# rpi_midi.net
KiCad netlist of a schematic drawn in EAGLE
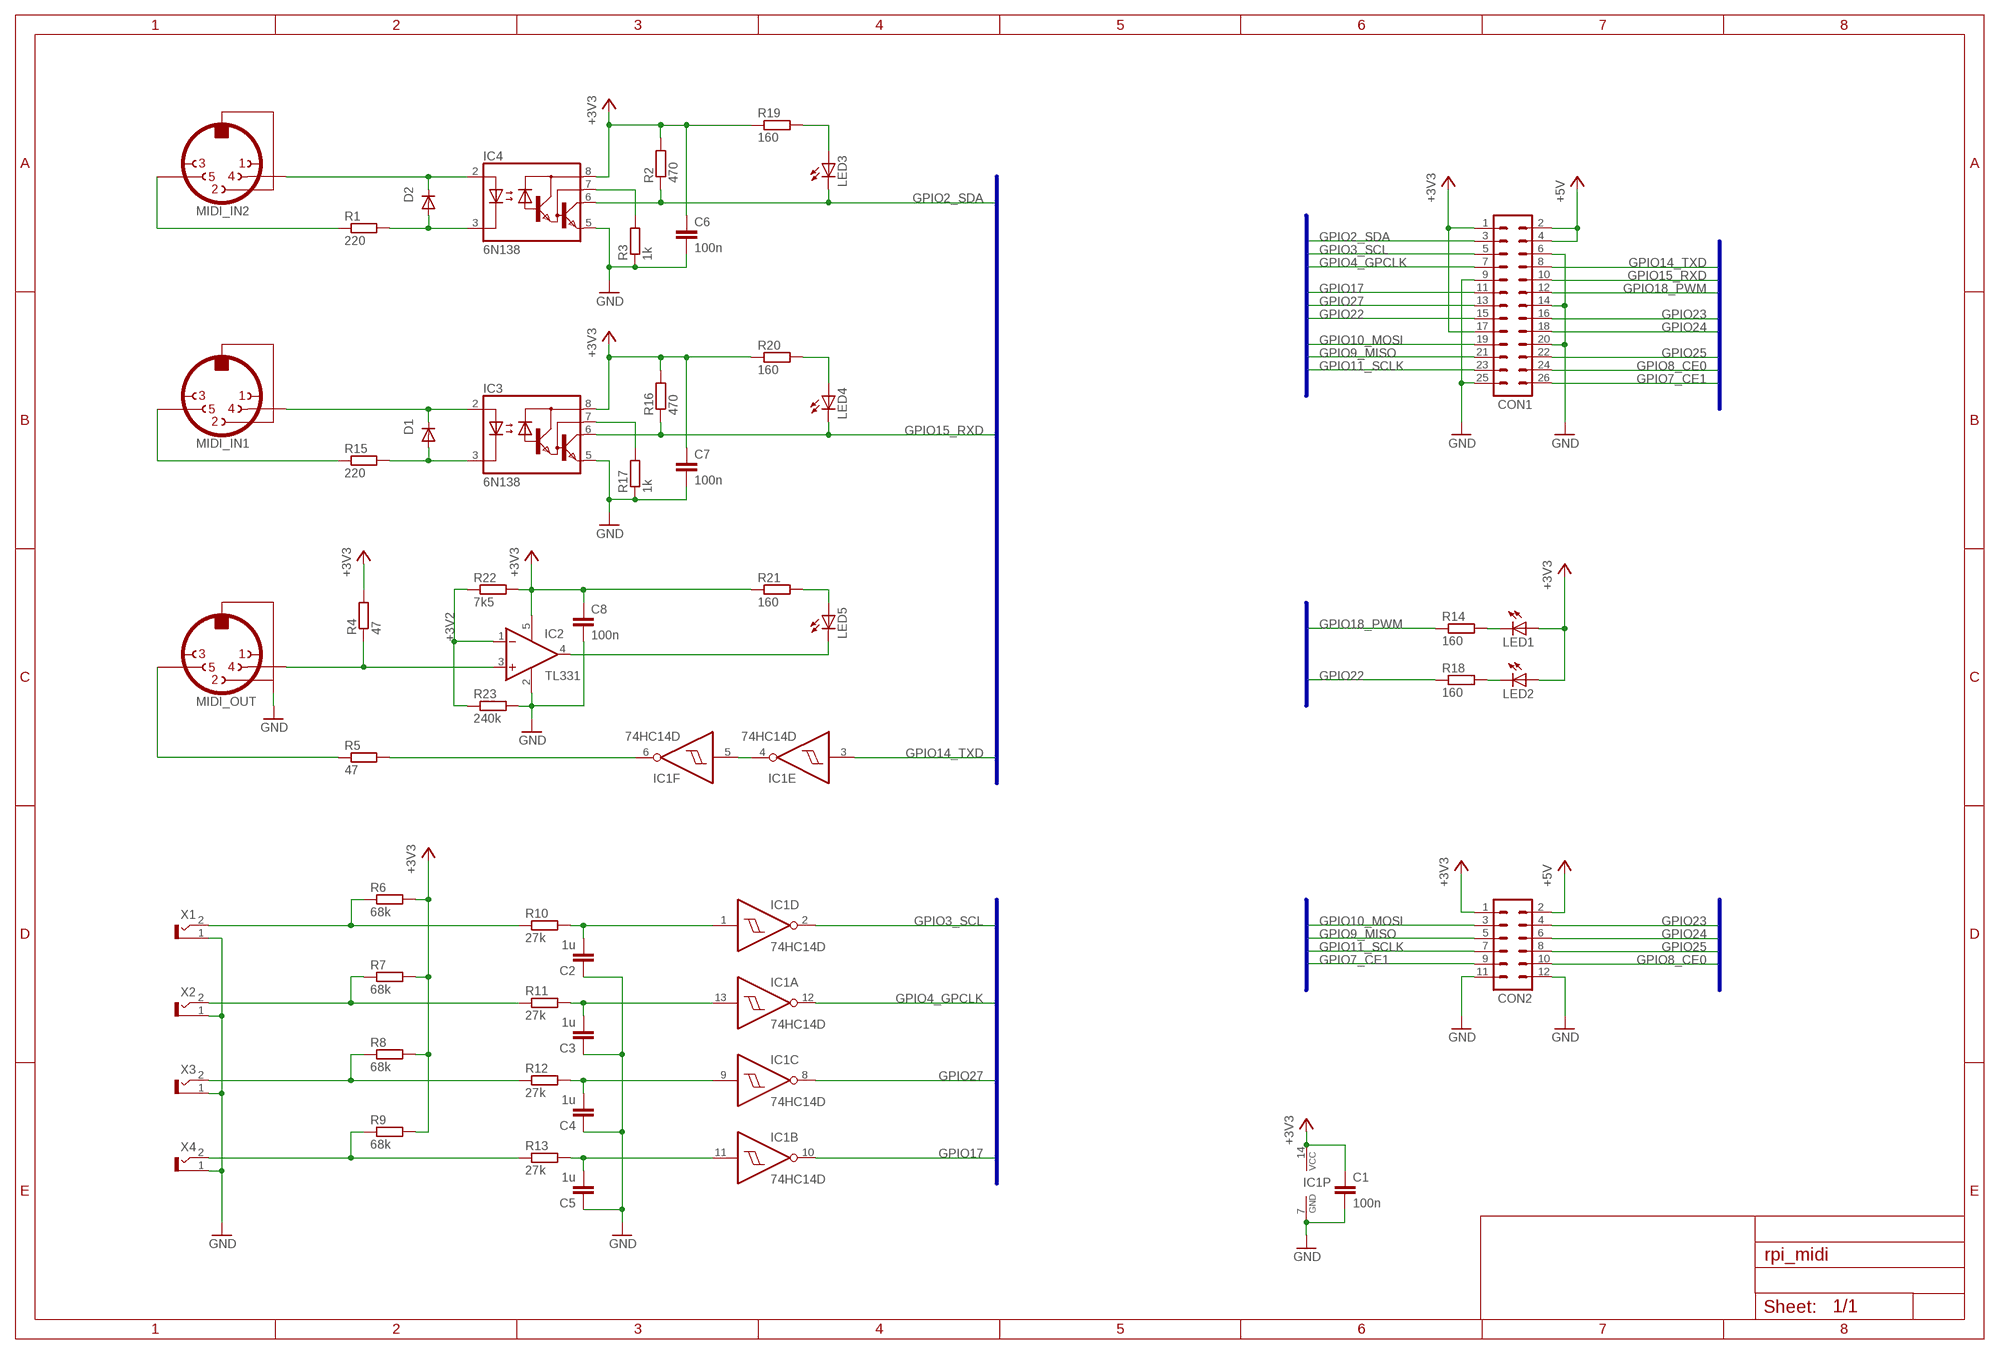
[diagram p0: schematic, sheet 1]

(export (version "E")
  (design (tool "Eeschema 10.0.6"))
  (components
    (comp (ref "C1")
      (value "100n")
      (footprint "eagle-import:C0603")
      (libsource (lib "eagle-import") (part "C-EUC0603"))
    )
    (comp (ref "C2")
      (value "1u")
      (footprint "eagle-import:C0603")
      (libsource (lib "eagle-import") (part "C-EUC0603"))
    )
    (comp (ref "C3")
      (value "1u")
      (footprint "eagle-import:C0603")
      (libsource (lib "eagle-import") (part "C-EUC0603"))
    )
    (comp (ref "C4")
      (value "1u")
      (footprint "eagle-import:C0603")
      (libsource (lib "eagle-import") (part "C-EUC0603"))
    )
    (comp (ref "C5")
      (value "1u")
      (footprint "eagle-import:C0603")
      (libsource (lib "eagle-import") (part "C-EUC0603"))
    )
    (comp (ref "C6")
      (value "100n")
      (footprint "eagle-import:C0603")
      (libsource (lib "eagle-import") (part "C-EUC0603"))
    )
    (comp (ref "C7")
      (value "100n")
      (footprint "eagle-import:C0603")
      (libsource (lib "eagle-import") (part "C-EUC0603"))
    )
    (comp (ref "C8")
      (value "100n")
      (footprint "eagle-import:C0603")
      (libsource (lib "eagle-import") (part "C-EUC0603"))
    )
    (comp (ref "CON1")
      (value "MA13-2")
      (footprint "eagle-import:MA13-2")
      (libsource (lib "eagle-import") (part "MA13-2"))
    )
    (comp (ref "CON2")
      (value "MA06-2")
      (footprint "eagle-import:MA06-2")
      (libsource (lib "eagle-import") (part "MA06-2"))
    )
    (comp (ref "D1")
      (value "1N4148SOD-323")
      (footprint "eagle-import:SOD323-R")
      (libsource (lib "eagle-import") (part "1N4148SOD-323"))
    )
    (comp (ref "D2")
      (value "1N4148SOD-323")
      (footprint "eagle-import:SOD323-R")
      (libsource (lib "eagle-import") (part "1N4148SOD-323"))
    )
    (comp (ref "IC1")
      (value "74HC14D")
      (footprint "eagle-import:SO14")
      (libsource (lib "eagle-import") (part "7414DHC"))
    )
    (comp (ref "IC2")
      (value "TL331")
      (footprint "eagle-import:SOT23-DBV")
      (libsource (lib "eagle-import") (part "TL331"))
    )
    (comp (ref "IC3")
      (value "6N138")
      (footprint "eagle-import:DIL08")
      (fields (field (name "MF") "VISHAY/TELEFUNKEN"))
      (libsource (lib "eagle-import") (part "6N138"))
    )
    (comp (ref "IC4")
      (value "6N138")
      (footprint "eagle-import:DIL08")
      (fields (field (name "MF") "VISHAY/TELEFUNKEN"))
      (libsource (lib "eagle-import") (part "6N138"))
    )
    (comp (ref "LED1")
      (value "LED2.54MM")
      (footprint "eagle-import:HEADER_2X1")
      (libsource (lib "eagle-import") (part "LED2.54MM"))
    )
    (comp (ref "LED2")
      (value "LED2.54MM")
      (footprint "eagle-import:HEADER_2X1")
      (libsource (lib "eagle-import") (part "LED2.54MM"))
    )
    (comp (ref "LED3")
      (value "LED2.54MM")
      (footprint "eagle-import:HEADER_2X1")
      (libsource (lib "eagle-import") (part "LED2.54MM"))
    )
    (comp (ref "LED4")
      (value "LED2.54MM")
      (footprint "eagle-import:HEADER_2X1")
      (libsource (lib "eagle-import") (part "LED2.54MM"))
    )
    (comp (ref "LED5")
      (value "LED2.54MM")
      (footprint "eagle-import:HEADER_2X1")
      (libsource (lib "eagle-import") (part "LED2.54MM"))
    )
    (comp (ref "MIDI_IN1")
      (value "MIDI_2PIN")
      (footprint "eagle-import:HEADER_2X1")
      (libsource (lib "eagle-import") (part "MIDI_2PIN"))
    )
    (comp (ref "MIDI_IN2")
      (value "MIDI_2PIN")
      (footprint "eagle-import:HEADER_2X1")
      (libsource (lib "eagle-import") (part "MIDI_2PIN"))
    )
    (comp (ref "MIDI_OUT")
      (value "MIDI_3PIN")
      (footprint "eagle-import:HEADER_3X1")
      (libsource (lib "eagle-import") (part "MIDI_3PIN"))
    )
    (comp (ref "R1")
      (value "220")
      (footprint "eagle-import:R0603")
      (libsource (lib "eagle-import") (part "R-EU_R0603"))
    )
    (comp (ref "R2")
      (value "470")
      (footprint "eagle-import:R0603")
      (libsource (lib "eagle-import") (part "R-EU_R0603"))
    )
    (comp (ref "R3")
      (value "1k")
      (footprint "eagle-import:R0603")
      (libsource (lib "eagle-import") (part "R-EU_R0603"))
    )
    (comp (ref "R4")
      (value "47")
      (footprint "eagle-import:R0603")
      (libsource (lib "eagle-import") (part "R-EU_R0603"))
    )
    (comp (ref "R5")
      (value "47")
      (footprint "eagle-import:R0603")
      (libsource (lib "eagle-import") (part "R-EU_R0603"))
    )
    (comp (ref "R6")
      (value "68k")
      (footprint "eagle-import:R0603")
      (libsource (lib "eagle-import") (part "R-EU_R0603"))
    )
    (comp (ref "R7")
      (value "68k")
      (footprint "eagle-import:R0603")
      (libsource (lib "eagle-import") (part "R-EU_R0603"))
    )
    (comp (ref "R8")
      (value "68k")
      (footprint "eagle-import:R0603")
      (libsource (lib "eagle-import") (part "R-EU_R0603"))
    )
    (comp (ref "R9")
      (value "68k")
      (footprint "eagle-import:R0603")
      (libsource (lib "eagle-import") (part "R-EU_R0603"))
    )
    (comp (ref "R10")
      (value "27k")
      (footprint "eagle-import:R0603")
      (libsource (lib "eagle-import") (part "R-EU_R0603"))
    )
    (comp (ref "R11")
      (value "27k")
      (footprint "eagle-import:R0603")
      (libsource (lib "eagle-import") (part "R-EU_R0603"))
    )
    (comp (ref "R12")
      (value "27k")
      (footprint "eagle-import:R0603")
      (libsource (lib "eagle-import") (part "R-EU_R0603"))
    )
    (comp (ref "R13")
      (value "27k")
      (footprint "eagle-import:R0603")
      (libsource (lib "eagle-import") (part "R-EU_R0603"))
    )
    (comp (ref "R14")
      (value "160")
      (footprint "eagle-import:R0603")
      (libsource (lib "eagle-import") (part "R-EU_R0603"))
    )
    (comp (ref "R15")
      (value "220")
      (footprint "eagle-import:R0603")
      (libsource (lib "eagle-import") (part "R-EU_R0603"))
    )
    (comp (ref "R16")
      (value "470")
      (footprint "eagle-import:R0603")
      (libsource (lib "eagle-import") (part "R-EU_R0603"))
    )
    (comp (ref "R17")
      (value "1k")
      (footprint "eagle-import:R0603")
      (libsource (lib "eagle-import") (part "R-EU_R0603"))
    )
    (comp (ref "R18")
      (value "160")
      (footprint "eagle-import:R0603")
      (libsource (lib "eagle-import") (part "R-EU_R0603"))
    )
    (comp (ref "R19")
      (value "160")
      (footprint "eagle-import:R0603")
      (libsource (lib "eagle-import") (part "R-EU_R0603"))
    )
    (comp (ref "R20")
      (value "160")
      (footprint "eagle-import:R0603")
      (libsource (lib "eagle-import") (part "R-EU_R0603"))
    )
    (comp (ref "R21")
      (value "160")
      (footprint "eagle-import:R0603")
      (libsource (lib "eagle-import") (part "R-EU_R0603"))
    )
    (comp (ref "R22")
      (value "7k5")
      (footprint "eagle-import:R0603")
      (libsource (lib "eagle-import") (part "R-EU_R0603"))
    )
    (comp (ref "R23")
      (value "240k")
      (footprint "eagle-import:R0603")
      (libsource (lib "eagle-import") (part "R-EU_R0603"))
    )
    (comp (ref "X1")
      (value "WBTOR12.54MM")
      (footprint "eagle-import:HEADER_2X1")
      (libsource (lib "eagle-import") (part "WBTOR12.54MM"))
    )
    (comp (ref "X2")
      (value "WBTOR12.54MM")
      (footprint "eagle-import:HEADER_2X1")
      (libsource (lib "eagle-import") (part "WBTOR12.54MM"))
    )
    (comp (ref "X3")
      (value "WBTOR12.54MM")
      (footprint "eagle-import:HEADER_2X1")
      (libsource (lib "eagle-import") (part "WBTOR12.54MM"))
    )
    (comp (ref "X4")
      (value "WBTOR12.54MM")
      (footprint "eagle-import:HEADER_2X1")
      (libsource (lib "eagle-import") (part "WBTOR12.54MM"))
    )
  )
  (nets
    (net (code "1") (name "+3V3") (class "Default")
      (node (ref "C1") (pin "1") (pinfunction "1_1") (pintype "passive"))
      (node (ref "C6") (pin "1") (pinfunction "1_1") (pintype "passive"))
      (node (ref "C7") (pin "1") (pinfunction "1_1") (pintype "passive"))
      (node (ref "C8") (pin "1") (pinfunction "1_1") (pintype "passive"))
      (node (ref "CON1") (pin "1") (pinfunction "1_1") (pintype "passive"))
      (node (ref "CON1") (pin "17") (pinfunction "17_17") (pintype "passive"))
      (node (ref "CON2") (pin "1") (pinfunction "1_1") (pintype "passive"))
      (node (ref "IC1") (pin "14") (pinfunction "VCC_14") (pintype "power_in"))
      (node (ref "IC2") (pin "5") (pinfunction "V+_5") (pintype "power_in"))
      (node (ref "IC3") (pin "8") (pinfunction "VCC_8") (pintype "passive"))
      (node (ref "IC4") (pin "8") (pinfunction "VCC_8") (pintype "passive"))
      (node (ref "LED1") (pin "1") (pinfunction "A_1") (pintype "passive"))
      (node (ref "LED2") (pin "1") (pinfunction "A_1") (pintype "passive"))
      (node (ref "R16") (pin "2") (pinfunction "2_2") (pintype "passive"))
      (node (ref "R19") (pin "1") (pinfunction "1_1") (pintype "passive"))
      (node (ref "R2") (pin "2") (pinfunction "2_2") (pintype "passive"))
      (node (ref "R20") (pin "1") (pinfunction "1_1") (pintype "passive"))
      (node (ref "R21") (pin "1") (pinfunction "1_1") (pintype "passive"))
      (node (ref "R22") (pin "2") (pinfunction "2_2") (pintype "passive"))
      (node (ref "R4") (pin "2") (pinfunction "2_2") (pintype "passive"))
      (node (ref "R6") (pin "2") (pinfunction "2_2") (pintype "passive"))
      (node (ref "R7") (pin "2") (pinfunction "2_2") (pintype "passive"))
      (node (ref "R8") (pin "2") (pinfunction "2_2") (pintype "passive"))
      (node (ref "R9") (pin "2") (pinfunction "2_2") (pintype "passive"))
    )
    (net (code "2") (name "+5V") (class "Default")
      (node (ref "CON1") (pin "2") (pinfunction "2_2") (pintype "passive"))
      (node (ref "CON1") (pin "4") (pinfunction "4_4") (pintype "passive"))
      (node (ref "CON2") (pin "2") (pinfunction "2_2") (pintype "passive"))
    )
    (net (code "3") (name "/+3V2") (class "Default")
      (node (ref "IC2") (pin "1") (pinfunction "-IN_1") (pintype "input"))
      (node (ref "R22") (pin "1") (pinfunction "1_1") (pintype "passive"))
      (node (ref "R23") (pin "1") (pinfunction "1_1") (pintype "passive"))
    )
    (net (code "4") (name "/GPIO2_SDA") (class "Default")
      (node (ref "CON1") (pin "3") (pinfunction "3_3") (pintype "passive"))
      (node (ref "IC4") (pin "6") (pinfunction "VO_6") (pintype "passive"))
      (node (ref "LED3") (pin "2") (pinfunction "C_2") (pintype "passive"))
      (node (ref "R2") (pin "1") (pinfunction "1_1") (pintype "passive"))
    )
    (net (code "5") (name "/GPIO3_SCL") (class "Default")
      (node (ref "CON1") (pin "5") (pinfunction "5_5") (pintype "passive"))
      (node (ref "IC1") (pin "2") (pinfunction "O_2") (pintype "output"))
    )
    (net (code "6") (name "/GPIO4_GPCLK") (class "Default")
      (node (ref "CON1") (pin "7") (pinfunction "7_7") (pintype "passive"))
      (node (ref "IC1") (pin "12") (pinfunction "O_12") (pintype "output"))
    )
    (net (code "7") (name "/GPIO7_CE1") (class "Default")
      (node (ref "CON1") (pin "26") (pinfunction "26_26") (pintype "passive"))
      (node (ref "CON2") (pin "9") (pinfunction "9_9") (pintype "passive"))
    )
    (net (code "8") (name "/GPIO8_CE0") (class "Default")
      (node (ref "CON1") (pin "24") (pinfunction "24_24") (pintype "passive"))
      (node (ref "CON2") (pin "10") (pinfunction "10_10") (pintype "passive"))
    )
    (net (code "9") (name "/GPIO9_MISO") (class "Default")
      (node (ref "CON1") (pin "21") (pinfunction "21_21") (pintype "passive"))
      (node (ref "CON2") (pin "5") (pinfunction "5_5") (pintype "passive"))
    )
    (net (code "10") (name "/GPIO10_MOSI") (class "Default")
      (node (ref "CON1") (pin "19") (pinfunction "19_19") (pintype "passive"))
      (node (ref "CON2") (pin "3") (pinfunction "3_3") (pintype "passive"))
    )
    (net (code "11") (name "/GPIO11_SCLK") (class "Default")
      (node (ref "CON1") (pin "23") (pinfunction "23_23") (pintype "passive"))
      (node (ref "CON2") (pin "7") (pinfunction "7_7") (pintype "passive"))
    )
    (net (code "12") (name "/GPIO14_TXD") (class "Default")
      (node (ref "CON1") (pin "8") (pinfunction "8_8") (pintype "passive"))
      (node (ref "IC1") (pin "3") (pinfunction "I_3") (pintype "input"))
    )
    (net (code "13") (name "/GPIO15_RXD") (class "Default")
      (node (ref "CON1") (pin "10") (pinfunction "10_10") (pintype "passive"))
      (node (ref "IC3") (pin "6") (pinfunction "VO_6") (pintype "passive"))
      (node (ref "LED4") (pin "2") (pinfunction "C_2") (pintype "passive"))
      (node (ref "R16") (pin "1") (pinfunction "1_1") (pintype "passive"))
    )
    (net (code "14") (name "/GPIO17") (class "Default")
      (node (ref "CON1") (pin "11") (pinfunction "11_11") (pintype "passive"))
      (node (ref "IC1") (pin "10") (pinfunction "O_10") (pintype "output"))
    )
    (net (code "15") (name "/GPIO18_PWM") (class "Default")
      (node (ref "CON1") (pin "12") (pinfunction "12_12") (pintype "passive"))
      (node (ref "R14") (pin "1") (pinfunction "1_1") (pintype "passive"))
    )
    (net (code "16") (name "/GPIO22") (class "Default")
      (node (ref "CON1") (pin "15") (pinfunction "15_15") (pintype "passive"))
      (node (ref "R18") (pin "1") (pinfunction "1_1") (pintype "passive"))
    )
    (net (code "17") (name "/GPIO23") (class "Default")
      (node (ref "CON1") (pin "16") (pinfunction "16_16") (pintype "passive"))
      (node (ref "CON2") (pin "4") (pinfunction "4_4") (pintype "passive"))
    )
    (net (code "18") (name "/GPIO24") (class "Default")
      (node (ref "CON1") (pin "18") (pinfunction "18_18") (pintype "passive"))
      (node (ref "CON2") (pin "6") (pinfunction "6_6") (pintype "passive"))
    )
    (net (code "19") (name "/GPIO25") (class "Default")
      (node (ref "CON1") (pin "22") (pinfunction "22_22") (pintype "passive"))
      (node (ref "CON2") (pin "8") (pinfunction "8_8") (pintype "passive"))
    )
    (net (code "20") (name "/GPIO27") (class "Default")
      (node (ref "CON1") (pin "13") (pinfunction "13_13") (pintype "passive"))
      (node (ref "IC1") (pin "8") (pinfunction "O_8") (pintype "output"))
    )
    (net (code "21") (name "GND") (class "Default")
      (node (ref "C1") (pin "2") (pinfunction "2_2") (pintype "passive"))
      (node (ref "C2") (pin "1") (pinfunction "1_1") (pintype "passive"))
      (node (ref "C3") (pin "1") (pinfunction "1_1") (pintype "passive"))
      (node (ref "C4") (pin "1") (pinfunction "1_1") (pintype "passive"))
      (node (ref "C5") (pin "1") (pinfunction "1_1") (pintype "passive"))
      (node (ref "C6") (pin "2") (pinfunction "2_2") (pintype "passive"))
      (node (ref "C7") (pin "2") (pinfunction "2_2") (pintype "passive"))
      (node (ref "C8") (pin "2") (pinfunction "2_2") (pintype "passive"))
      (node (ref "CON1") (pin "14") (pinfunction "14_14") (pintype "passive"))
      (node (ref "CON1") (pin "20") (pinfunction "20_20") (pintype "passive"))
      (node (ref "CON1") (pin "25") (pinfunction "25_25") (pintype "passive"))
      (node (ref "CON1") (pin "6") (pinfunction "6_6") (pintype "passive"))
      (node (ref "CON1") (pin "9") (pinfunction "9_9") (pintype "passive"))
      (node (ref "CON2") (pin "11") (pinfunction "11_11") (pintype "passive"))
      (node (ref "CON2") (pin "12") (pinfunction "12_12") (pintype "passive"))
      (node (ref "IC1") (pin "7") (pinfunction "GND_7") (pintype "power_in"))
      (node (ref "IC2") (pin "2") (pinfunction "V-_2") (pintype "power_in"))
      (node (ref "IC3") (pin "5") (pinfunction "GND_5") (pintype "passive"))
      (node (ref "IC4") (pin "5") (pinfunction "GND_5") (pintype "passive"))
      (node (ref "MIDI_OUT") (pin "3") (pinfunction "PE_3") (pintype "power_in"))
      (node (ref "R17") (pin "1") (pinfunction "1_1") (pintype "passive"))
      (node (ref "R23") (pin "2") (pinfunction "2_2") (pintype "passive"))
      (node (ref "R3") (pin "1") (pinfunction "1_1") (pintype "passive"))
      (node (ref "X1") (pin "1") (pinfunction "S_1") (pintype "passive"))
      (node (ref "X2") (pin "1") (pinfunction "S_1") (pintype "passive"))
      (node (ref "X3") (pin "1") (pinfunction "S_1") (pintype "passive"))
      (node (ref "X4") (pin "1") (pinfunction "S_1") (pintype "passive"))
    )
    (net (code "22") (name "Net-(IC1A-I)") (class "Default")
      (node (ref "C3") (pin "2") (pinfunction "2_2") (pintype "passive"))
      (node (ref "IC1") (pin "13") (pinfunction "I_13") (pintype "input"))
      (node (ref "R11") (pin "2") (pinfunction "2_2") (pintype "passive"))
    )
    (net (code "23") (name "Net-(IC1B-I)") (class "Default")
      (node (ref "C5") (pin "2") (pinfunction "2_2") (pintype "passive"))
      (node (ref "IC1") (pin "11") (pinfunction "I_11") (pintype "input"))
      (node (ref "R13") (pin "2") (pinfunction "2_2") (pintype "passive"))
    )
    (net (code "24") (name "Net-(IC1C-I)") (class "Default")
      (node (ref "C4") (pin "2") (pinfunction "2_2") (pintype "passive"))
      (node (ref "IC1") (pin "9") (pinfunction "I_9") (pintype "input"))
      (node (ref "R12") (pin "2") (pinfunction "2_2") (pintype "passive"))
    )
    (net (code "25") (name "Net-(IC1D-I)") (class "Default")
      (node (ref "C2") (pin "2") (pinfunction "2_2") (pintype "passive"))
      (node (ref "IC1") (pin "1") (pinfunction "I_1") (pintype "input"))
      (node (ref "R10") (pin "2") (pinfunction "2_2") (pintype "passive"))
    )
    (net (code "26") (name "Net-(IC1E-O)") (class "Default")
      (node (ref "IC1") (pin "4") (pinfunction "O_4") (pintype "output"))
      (node (ref "IC1") (pin "5") (pinfunction "I_5") (pintype "input"))
    )
    (net (code "27") (name "Net-(IC1F-O)") (class "Default")
      (node (ref "IC1") (pin "6") (pinfunction "O_6") (pintype "output"))
      (node (ref "R5") (pin "2") (pinfunction "2_2") (pintype "passive"))
    )
    (net (code "28") (name "Net-(IC2-+IN)") (class "Default")
      (node (ref "IC2") (pin "3") (pinfunction "+IN_3") (pintype "input"))
      (node (ref "MIDI_OUT") (pin "1") (pinfunction "4_1") (pintype "passive"))
      (node (ref "R4") (pin "1") (pinfunction "1_1") (pintype "passive"))
    )
    (net (code "29") (name "Net-(IC2-OUT)") (class "Default")
      (node (ref "IC2") (pin "4") (pinfunction "OUT_4") (pintype "output"))
      (node (ref "LED5") (pin "2") (pinfunction "C_2") (pintype "passive"))
    )
    (net (code "30") (name "Net-(IC3-A)") (class "Default")
      (node (ref "D1") (pin "C") (pinfunction "C_C") (pintype "passive"))
      (node (ref "IC3") (pin "2") (pinfunction "A_2") (pintype "passive"))
      (node (ref "MIDI_IN1") (pin "1") (pinfunction "4_1") (pintype "passive"))
    )
    (net (code "31") (name "Net-(IC3-C)") (class "Default")
      (node (ref "D1") (pin "A") (pinfunction "A_A") (pintype "passive"))
      (node (ref "IC3") (pin "3") (pinfunction "C_3") (pintype "passive"))
      (node (ref "R15") (pin "2") (pinfunction "2_2") (pintype "passive"))
    )
    (net (code "32") (name "Net-(IC3-VB)") (class "Default")
      (node (ref "IC3") (pin "7") (pinfunction "VB_7") (pintype "passive"))
      (node (ref "R17") (pin "2") (pinfunction "2_2") (pintype "passive"))
    )
    (net (code "33") (name "Net-(IC4-A)") (class "Default")
      (node (ref "D2") (pin "C") (pinfunction "C_C") (pintype "passive"))
      (node (ref "IC4") (pin "2") (pinfunction "A_2") (pintype "passive"))
      (node (ref "MIDI_IN2") (pin "1") (pinfunction "4_1") (pintype "passive"))
    )
    (net (code "34") (name "Net-(IC4-C)") (class "Default")
      (node (ref "D2") (pin "A") (pinfunction "A_A") (pintype "passive"))
      (node (ref "IC4") (pin "3") (pinfunction "C_3") (pintype "passive"))
      (node (ref "R1") (pin "2") (pinfunction "2_2") (pintype "passive"))
    )
    (net (code "35") (name "Net-(IC4-VB)") (class "Default")
      (node (ref "IC4") (pin "7") (pinfunction "VB_7") (pintype "passive"))
      (node (ref "R3") (pin "2") (pinfunction "2_2") (pintype "passive"))
    )
    (net (code "36") (name "Net-(LED1-C)") (class "Default")
      (node (ref "LED1") (pin "2") (pinfunction "C_2") (pintype "passive"))
      (node (ref "R14") (pin "2") (pinfunction "2_2") (pintype "passive"))
    )
    (net (code "37") (name "Net-(LED2-C)") (class "Default")
      (node (ref "LED2") (pin "2") (pinfunction "C_2") (pintype "passive"))
      (node (ref "R18") (pin "2") (pinfunction "2_2") (pintype "passive"))
    )
    (net (code "38") (name "Net-(LED3-A)") (class "Default")
      (node (ref "LED3") (pin "1") (pinfunction "A_1") (pintype "passive"))
      (node (ref "R19") (pin "2") (pinfunction "2_2") (pintype "passive"))
    )
    (net (code "39") (name "Net-(LED4-A)") (class "Default")
      (node (ref "LED4") (pin "1") (pinfunction "A_1") (pintype "passive"))
      (node (ref "R20") (pin "2") (pinfunction "2_2") (pintype "passive"))
    )
    (net (code "40") (name "Net-(LED5-A)") (class "Default")
      (node (ref "LED5") (pin "1") (pinfunction "A_1") (pintype "passive"))
      (node (ref "R21") (pin "2") (pinfunction "2_2") (pintype "passive"))
    )
    (net (code "41") (name "Net-(MIDI_IN1-5)") (class "Default")
      (node (ref "MIDI_IN1") (pin "2") (pinfunction "5_2") (pintype "passive"))
      (node (ref "R15") (pin "1") (pinfunction "1_1") (pintype "passive"))
    )
    (net (code "42") (name "Net-(MIDI_IN2-5)") (class "Default")
      (node (ref "MIDI_IN2") (pin "2") (pinfunction "5_2") (pintype "passive"))
      (node (ref "R1") (pin "1") (pinfunction "1_1") (pintype "passive"))
    )
    (net (code "43") (name "Net-(MIDI_OUT-5)") (class "Default")
      (node (ref "MIDI_OUT") (pin "2") (pinfunction "5_2") (pintype "passive"))
      (node (ref "R5") (pin "1") (pinfunction "1_1") (pintype "passive"))
    )
    (net (code "44") (name "Net-(X1-T)") (class "Default")
      (node (ref "R10") (pin "1") (pinfunction "1_1") (pintype "passive"))
      (node (ref "R6") (pin "1") (pinfunction "1_1") (pintype "passive"))
      (node (ref "X1") (pin "2") (pinfunction "T_2") (pintype "passive"))
    )
    (net (code "45") (name "Net-(X2-T)") (class "Default")
      (node (ref "R11") (pin "1") (pinfunction "1_1") (pintype "passive"))
      (node (ref "R7") (pin "1") (pinfunction "1_1") (pintype "passive"))
      (node (ref "X2") (pin "2") (pinfunction "T_2") (pintype "passive"))
    )
    (net (code "46") (name "Net-(X3-T)") (class "Default")
      (node (ref "R12") (pin "1") (pinfunction "1_1") (pintype "passive"))
      (node (ref "R8") (pin "1") (pinfunction "1_1") (pintype "passive"))
      (node (ref "X3") (pin "2") (pinfunction "T_2") (pintype "passive"))
    )
    (net (code "47") (name "Net-(X4-T)") (class "Default")
      (node (ref "R13") (pin "1") (pinfunction "1_1") (pintype "passive"))
      (node (ref "R9") (pin "1") (pinfunction "1_1") (pintype "passive"))
      (node (ref "X4") (pin "2") (pinfunction "T_2") (pintype "passive"))
    )
  )
)
